# MCU.net
KiCad netlist of a schematic drawn in Altium Designer
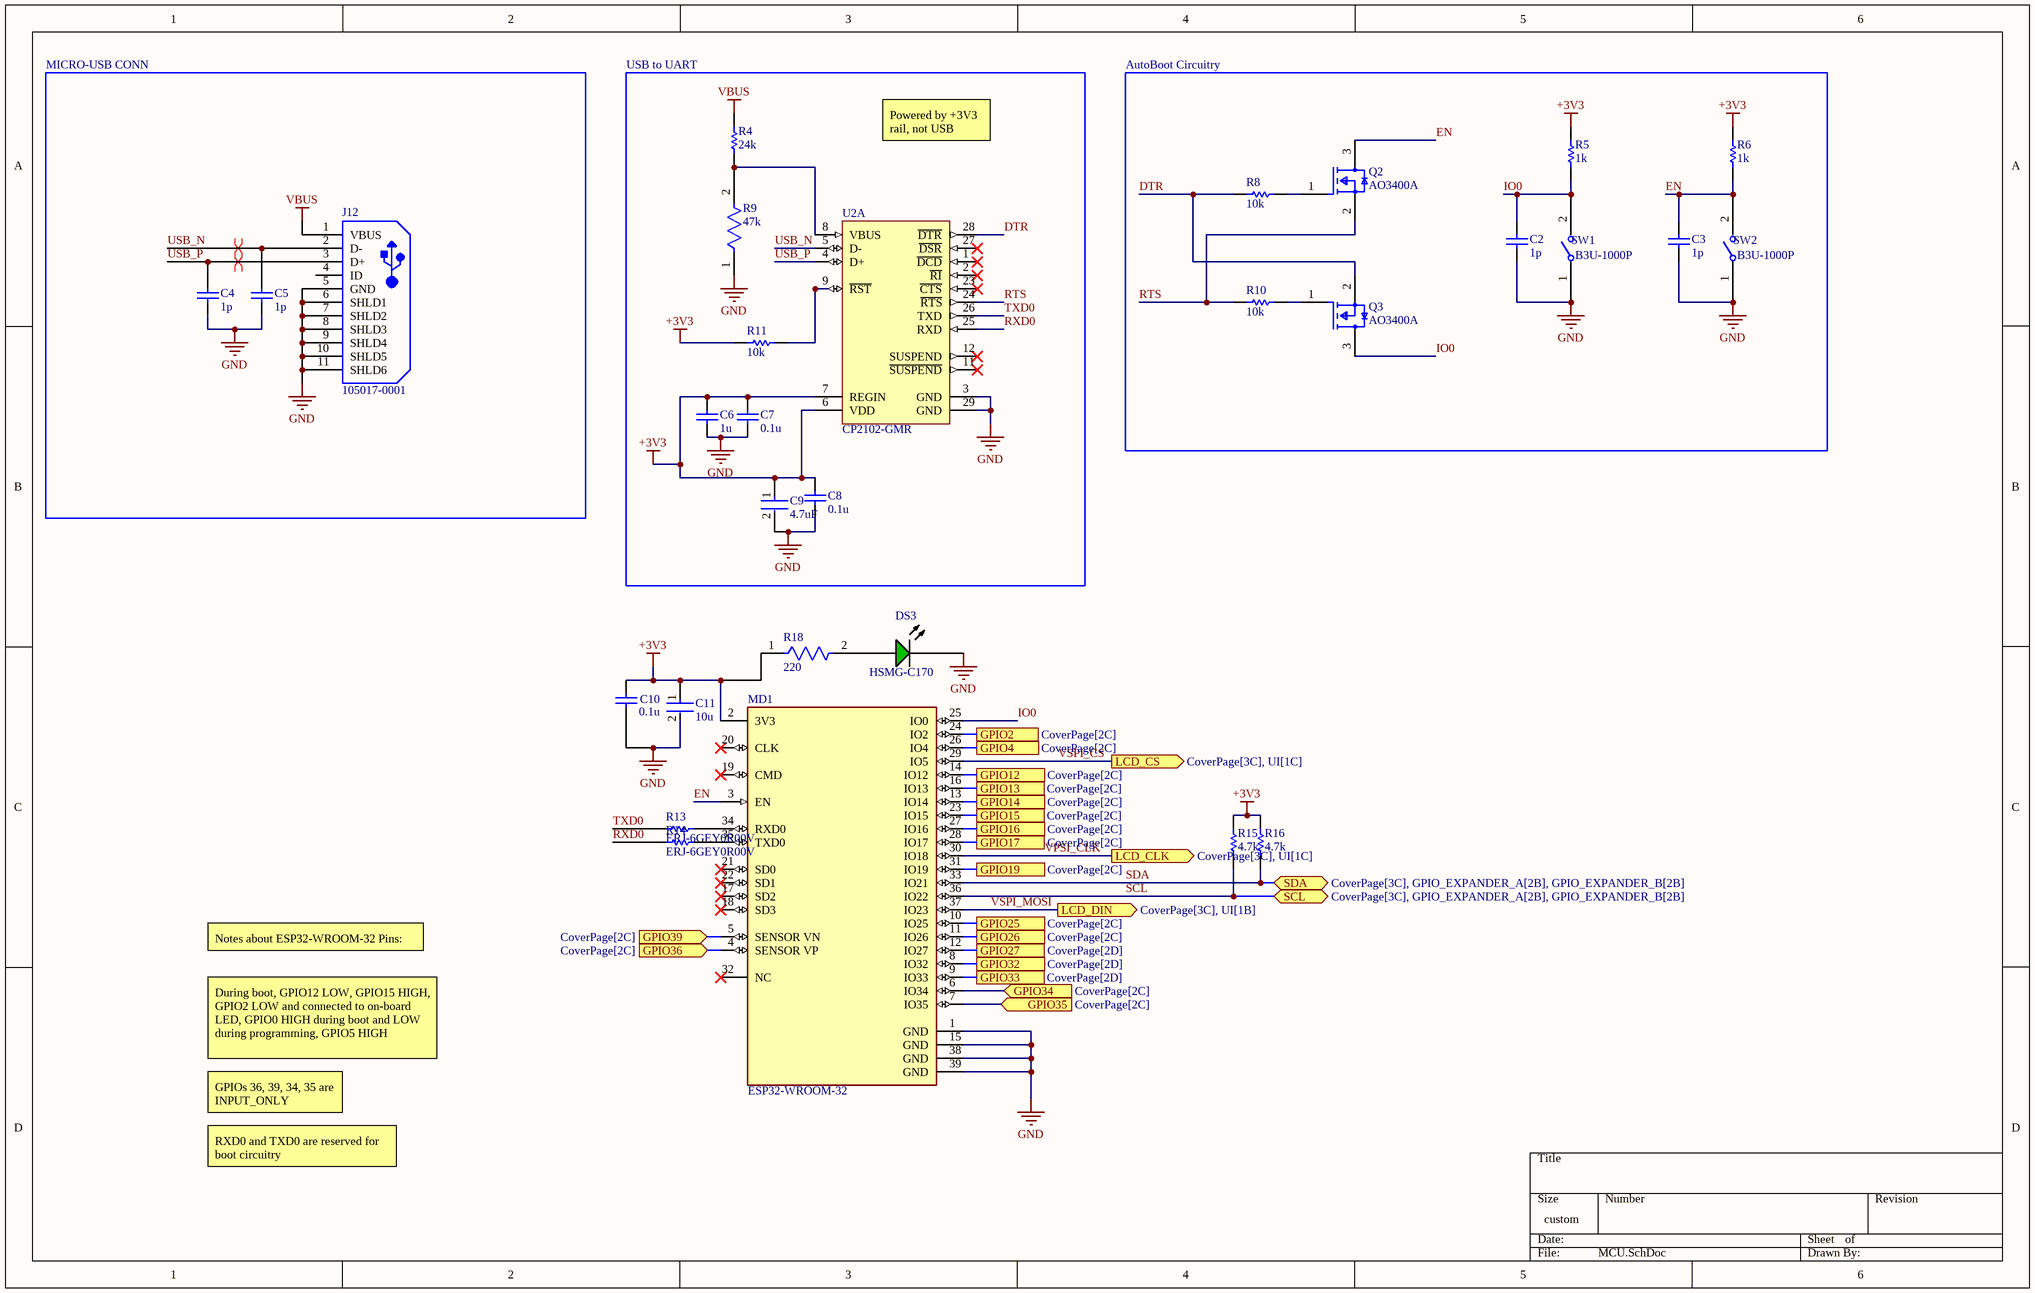
[diagram p0: MCU.SchDoc]

(export (version "E")
  (design (tool "Eeschema 10.0.6"))
  (components
    (comp (ref "C2")
      (value "1p")
      (footprint "CAPC2013X140X50LL20T25")
      (fields
        (field (name "PART NUMBER") "08055A1R0CAT2A")
        (field (name "MANUFACTURER") "AVX Interconnect / Elco")
      )
      (libsource (lib "Altium Content Vault") (part "CAP"))
    )
    (comp (ref "C3")
      (value "1p")
      (footprint "CAPC2013X140X50LL20T25")
      (fields
        (field (name "PART NUMBER") "08055A1R0CAT2A")
        (field (name "MANUFACTURER") "AVX Interconnect / Elco")
      )
      (libsource (lib "Altium Content Vault") (part "CAP"))
    )
    (comp (ref "C4")
      (value "1p")
      (footprint "CAPC2013X140X50LL20T25")
      (fields
        (field (name "PART NUMBER") "08055A1R0CAT2A")
        (field (name "MANUFACTURER") "AVX Interconnect / Elco")
      )
      (libsource (lib "Altium Content Vault") (part "CAP"))
    )
    (comp (ref "C5")
      (value "1p")
      (footprint "CAPC2013X140X50LL20T25")
      (fields
        (field (name "PART NUMBER") "08055A1R0CAT2A")
        (field (name "MANUFACTURER") "AVX Interconnect / Elco")
      )
      (libsource (lib "Altium Content Vault") (part "CAP"))
    )
    (comp (ref "C6")
      (value "1u")
      (footprint "CAPC2013X145X50LL20T25")
      (fields (field (name "MANUFACTURER") "Kemet") (field (name "PART NUMBER") "C0805C105K4PACTU"))
      (libsource (lib "Altium Content Vault") (part "CAP"))
    )
    (comp (ref "C7")
      (value "0.1u")
      (footprint "CAPC2013X94X50LL20T25")
      (fields
        (field (name "MANUFACTURER") "AVX Interconnect / Elco")
        (field (name "PART NUMBER") "08055C104JAZ2A")
      )
      (libsource (lib "Altium Content Vault") (part "CAP"))
    )
    (comp (ref "C8")
      (value "0.1u")
      (footprint "CAPC2013X94X50LL20T25")
      (fields
        (field (name "MANUFACTURER") "AVX Interconnect / Elco")
        (field (name "PART NUMBER") "08055C104JAZ2A")
      )
      (libsource (lib "Altium Content Vault") (part "CAP"))
    )
    (comp (ref "C9")
      (value "4.7uF")
      (footprint "FP-CL21-IPC_A")
      (description "CL21 Series 0805 4.7uF 25V ±10% Tolerance X5R Multilayer Ceramic Chip Capacitor")
      (fields (field (name "TOLERANCE") "10%"))
      (libsource (lib "Altium Content Vault") (part "b4654b650e69147ec39a6b967a45e02"))
    )
    (comp (ref "C10")
      (value "0.1u")
      (footprint "CAPC2013X94X50LL20T25")
      (fields
        (field (name "MANUFACTURER") "AVX Interconnect / Elco")
        (field (name "PART NUMBER") "08055C104JAZ2A")
      )
      (libsource (lib "Altium Content Vault") (part "CAP"))
    )
    (comp (ref "C11")
      (value "10u")
      (footprint "FP-C0805C-DG-MFG")
      (description "CAP CER 10UF 10V X5R 0805")
      (fields (field (name "TOLERANCE") "10%") (field (name "MANUFACTURER PART NUMBER") "C0805C106K8PACTU"))
      (libsource (lib "Altium Content Vault") (part "11868f565c42a9108669ba33697ecf6"))
    )
    (comp (ref "DS3")
      (value "HSMG-C170")
      (footprint "AVAG-HSMX-C170_V")
      (description "Chip LED, Green, 2.2 V, -40 to 85 degC, 2-Pin SMD, Pb-Free, Tape and Reel")
      (fields (field (name "MANUFACTURER") "Avago"))
      (libsource (lib "Altium Content Vault") (part "LED_GREEN_A1K2-2"))
    )
    (comp (ref "J12")
      (value "105017-0001")
      (footprint "USB-MICRO-B_V")
      (fields (field (name "MANUFACTURER") "Molex"))
      (libsource (lib "Altium Content Vault") (part "USB-5-6SHLD"))
    )
    (comp (ref "MD1")
      (value "ESP32-WROOM-32")
      (footprint "FP-ESP32-WROOM-32-MFG")
      (description "RX TXRX MOD WIFI SURFACE MOUNT")
      (libsource (lib "Altium Content Vault") (part "ee866abf0b6c51247b7f5cdebf2f250"))
    )
    (comp (ref "Q2")
      (value "AO3400A")
      (footprint "FP-SOT23-MFG")
      (description "MOSFET N-CH 30V 5.7A SOT23")
      (libsource (lib "Altium Content Vault") (part "0a9ea7c96deaaede766a5b531c28de0"))
    )
    (comp (ref "Q3")
      (value "AO3400A")
      (footprint "FP-SOT23-MFG")
      (description "MOSFET N-CH 30V 5.7A SOT23")
      (libsource (lib "Altium Content Vault") (part "0a9ea7c96deaaede766a5b531c28de0"))
    )
    (comp (ref "R4")
      (value "24k")
      (footprint "RESC2013X60X40LL20T25")
      (fields (field (name "PART NUMBER") "ERA6AEB243V") (field (name "MANUFACTURER") "Panasonic"))
      (libsource (lib "Altium Content Vault") (part "RES"))
    )
    (comp (ref "R5")
      (value "1k")
      (footprint "RESC2013X60X35ML10T20")
      (description "Chip Resistor, 1 KOhm, +/- 1%, 125 mW, -55 to 155 degC, 0805 (2012 Metric), RoHS, Tape and Reel")
      (fields (field (name "TOLERANCE") "1%") (field (name "MANUFACTURER") "Yageo"))
      (libsource (lib "Altium Content Vault") (part "RES-2"))
    )
    (comp (ref "R6")
      (value "1k")
      (footprint "RESC2013X60X35ML10T20")
      (description "Chip Resistor, 1 KOhm, +/- 1%, 125 mW, -55 to 155 degC, 0805 (2012 Metric), RoHS, Tape and Reel")
      (fields (field (name "TOLERANCE") "1%") (field (name "MANUFACTURER") "Yageo"))
      (libsource (lib "Altium Content Vault") (part "RES-2"))
    )
    (comp (ref "R8")
      (value "10k")
      (footprint "RESC2013X60X40LL20T25_A")
      (fields (field (name "TOLERANCE") "0.1%") (field (name "MANUFACTURER") "Panasonic"))
      (libsource (lib "Altium Content Vault") (part "RES-2"))
    )
    (comp (ref "R9")
      (value "47k")
      (footprint "FP-ERA6A-MFG")
      (fields (field (name "TOLERANCE") "0.1%"))
      (libsource (lib "Altium Content Vault") (part "1029c3af85768c4190bb7ad29bc67b5"))
    )
    (comp (ref "R10")
      (value "10k")
      (footprint "RESC2013X60X40LL20T25_A")
      (fields (field (name "TOLERANCE") "0.1%") (field (name "MANUFACTURER") "Panasonic"))
      (libsource (lib "Altium Content Vault") (part "RES-2"))
    )
    (comp (ref "R11")
      (value "10k")
      (footprint "RESC2013X60X40LL20T25_A")
      (fields (field (name "TOLERANCE") "0.1%") (field (name "MANUFACTURER") "Panasonic"))
      (libsource (lib "Altium Content Vault") (part "RES-2"))
    )
    (comp (ref "R13")
      (value "ERJ-6GEY0R00V")
      (footprint "RESC2013X70X40NL20T20")
      (description "Chip Resistor, 0 Ohm, +/- 1%, 0.125 W, -55 to 155 degC, 0805 (2012 Metric), RoHS, Tape and Reel")
      (fields (field (name "TOLERANCE") "5%"))
      (libsource (lib "Altium Content Vault") (part "RES-2"))
    )
    (comp (ref "R14")
      (value "ERJ-6GEY0R00V")
      (footprint "RESC2013X70X40NL20T20")
      (description "Chip Resistor, 0 Ohm, +/- 1%, 0.125 W, -55 to 155 degC, 0805 (2012 Metric), RoHS, Tape and Reel")
      (fields (field (name "TOLERANCE") "5%"))
      (libsource (lib "Altium Content Vault") (part "RES-2"))
    )
    (comp (ref "R15")
      (value "4.7k")
      (footprint "YAGO-RC0805_M")
      (fields
        (field (name "TOLERANCE") "+/- 1%")
        (field (name "PARTNUMBER") "RC0805FR-074K7L")
        (field (name "POWER") "0.125 W")
      )
      (libsource (lib "Altium Content Vault") (part "YAGO-RES-2"))
    )
    (comp (ref "R16")
      (value "4.7k")
      (footprint "YAGO-RC0805_M")
      (fields
        (field (name "TOLERANCE") "+/- 1%")
        (field (name "PARTNUMBER") "RC0805FR-074K7L")
        (field (name "POWER") "0.125 W")
      )
      (libsource (lib "Altium Content Vault") (part "YAGO-RES-2"))
    )
    (comp (ref "R18")
      (value "220")
      (footprint "FP-CRCW0805-e3-MFG")
      (description "RES Thick Film, 330Ω, 1%, 0.125W, 100ppm/°C, 0805")
      (fields (field (name "TOLERANCE") "1%"))
      (libsource (lib "Altium Content Vault") (part "1029c3af85768c4190bb7ad29bc67b5"))
    )
    (comp (ref "SW1")
      (value "B3U-1000P")
      (footprint "FP-B3U-1000P-MFG")
      (description "SWITCH TACTILE SPST-NO 0.05A 12V")
      (libsource (lib "Altium Content Vault") (part "ae622034201233ca1abcedc05908f33"))
    )
    (comp (ref "SW2")
      (value "B3U-1000P")
      (footprint "FP-B3U-1000P-MFG")
      (description "SWITCH TACTILE SPST-NO 0.05A 12V")
      (libsource (lib "Altium Content Vault") (part "ae622034201233ca1abcedc05908f33"))
    )
    (comp (ref "U2")
      (value "CP2102-GMR")
      (footprint "SLAB-QFN-28-3125x3125TP_M")
      (description "Single-Chip USB to URAT Bridge, 3.3 V, -40 to 85 degC, 28-Pin QFN, RoHS, Tape and Reel")
      (fields (field (name "MANUFACTURER") "Silicon Labs"))
      (libsource (lib "Altium Content Vault") (part "SLAB-CP210X-QFN-28-29"))
    )
  )
  (nets
    (net (code "1") (name "+3V3") (class "Default")
      (node (ref "C10") (pin "2") (pinfunction "2_2") (pintype "passive"))
      (node (ref "C11") (pin "1") (pinfunction "1_1") (pintype "passive"))
      (node (ref "C6") (pin "2") (pinfunction "2_2") (pintype "passive"))
      (node (ref "C7") (pin "2") (pinfunction "2_2") (pintype "passive"))
      (node (ref "C8") (pin "2") (pinfunction "2_2") (pintype "passive"))
      (node (ref "C9") (pin "1") (pinfunction "1_1") (pintype "passive"))
      (node (ref "MD1") (pin "2") (pinfunction "3V3_2") (pintype "power_in"))
      (node (ref "R11") (pin "1") (pinfunction "1_1") (pintype "passive"))
      (node (ref "R15") (pin "2") (pinfunction "2_2") (pintype "passive"))
      (node (ref "R16") (pin "2") (pinfunction "2_2") (pintype "passive"))
      (node (ref "R18") (pin "1") (pinfunction "1_1") (pintype "passive"))
      (node (ref "R5") (pin "2") (pinfunction "2_2") (pintype "passive"))
      (node (ref "R6") (pin "2") (pinfunction "2_2") (pintype "passive"))
      (node (ref "U2") (pin "6") (pinfunction "VDD_6") (pintype "power_in"))
      (node (ref "U2") (pin "7") (pinfunction "REGIN_7") (pintype "power_in"))
    )
    (net (code "2") (name "/DTR") (class "Default")
      (node (ref "Q3") (pin "2") (pinfunction "S_2") (pintype "passive"))
      (node (ref "R8") (pin "1") (pinfunction "1_1") (pintype "passive"))
      (node (ref "U2") (pin "28") (pinfunction "~{DTR}_28") (pintype "output"))
    )
    (net (code "3") (name "/EN") (class "Default")
      (node (ref "C3") (pin "2") (pinfunction "2_2") (pintype "passive"))
      (node (ref "MD1") (pin "3") (pinfunction "EN_3") (pintype "input"))
      (node (ref "Q2") (pin "3") (pinfunction "D_3") (pintype "passive"))
      (node (ref "R6") (pin "1") (pinfunction "1_1") (pintype "passive"))
      (node (ref "SW2") (pin "2") (pinfunction "2_2") (pintype "passive"))
    )
    (net (code "4") (name "/GPIO2") (class "Default")
      (node (ref "MD1") (pin "24") (pinfunction "IO2_24") (pintype "bidirectional"))
    )
    (net (code "5") (name "/GPIO4") (class "Default")
      (node (ref "MD1") (pin "26") (pinfunction "IO4_26") (pintype "bidirectional"))
    )
    (net (code "6") (name "/GPIO12") (class "Default")
      (node (ref "MD1") (pin "14") (pinfunction "IO12_14") (pintype "bidirectional"))
    )
    (net (code "7") (name "/GPIO13") (class "Default")
      (node (ref "MD1") (pin "16") (pinfunction "IO13_16") (pintype "bidirectional"))
    )
    (net (code "8") (name "/GPIO14") (class "Default")
      (node (ref "MD1") (pin "13") (pinfunction "IO14_13") (pintype "bidirectional"))
    )
    (net (code "9") (name "/GPIO15") (class "Default")
      (node (ref "MD1") (pin "23") (pinfunction "IO15_23") (pintype "bidirectional"))
    )
    (net (code "10") (name "/GPIO16") (class "Default")
      (node (ref "MD1") (pin "27") (pinfunction "IO16_27") (pintype "bidirectional"))
    )
    (net (code "11") (name "/GPIO17") (class "Default")
      (node (ref "MD1") (pin "28") (pinfunction "IO17_28") (pintype "bidirectional"))
    )
    (net (code "12") (name "/GPIO19") (class "Default")
      (node (ref "MD1") (pin "31") (pinfunction "IO19_31") (pintype "bidirectional"))
    )
    (net (code "13") (name "/GPIO25") (class "Default")
      (node (ref "MD1") (pin "10") (pinfunction "IO25_10") (pintype "bidirectional"))
    )
    (net (code "14") (name "/GPIO26") (class "Default")
      (node (ref "MD1") (pin "11") (pinfunction "IO26_11") (pintype "bidirectional"))
    )
    (net (code "15") (name "/GPIO27") (class "Default")
      (node (ref "MD1") (pin "12") (pinfunction "IO27_12") (pintype "bidirectional"))
    )
    (net (code "16") (name "/GPIO32") (class "Default")
      (node (ref "MD1") (pin "8") (pinfunction "IO32_8") (pintype "bidirectional"))
    )
    (net (code "17") (name "/GPIO33") (class "Default")
      (node (ref "MD1") (pin "9") (pinfunction "IO33_9") (pintype "bidirectional"))
    )
    (net (code "18") (name "/GPIO34") (class "Default")
      (node (ref "MD1") (pin "6") (pinfunction "IO34_6") (pintype "bidirectional"))
    )
    (net (code "19") (name "/GPIO35") (class "Default")
      (node (ref "MD1") (pin "7") (pinfunction "IO35_7") (pintype "bidirectional"))
    )
    (net (code "20") (name "/GPIO36") (class "Default")
      (node (ref "MD1") (pin "4") (pinfunction "SENSOR_VP_4") (pintype "bidirectional"))
    )
    (net (code "21") (name "/GPIO39") (class "Default")
      (node (ref "MD1") (pin "5") (pinfunction "SENSOR_VN_5") (pintype "bidirectional"))
    )
    (net (code "22") (name "/IO0") (class "Default")
      (node (ref "C2") (pin "2") (pinfunction "2_2") (pintype "passive"))
      (node (ref "MD1") (pin "25") (pinfunction "IO0_25") (pintype "bidirectional"))
      (node (ref "Q3") (pin "3") (pinfunction "D_3") (pintype "passive"))
      (node (ref "R5") (pin "1") (pinfunction "1_1") (pintype "passive"))
      (node (ref "SW1") (pin "2") (pinfunction "2_2") (pintype "passive"))
    )
    (net (code "23") (name "/RTS") (class "Default")
      (node (ref "Q2") (pin "2") (pinfunction "S_2") (pintype "passive"))
      (node (ref "R10") (pin "1") (pinfunction "1_1") (pintype "passive"))
      (node (ref "U2") (pin "24") (pinfunction "~{RTS}_24") (pintype "output"))
    )
    (net (code "24") (name "/RXD0") (class "Default")
      (node (ref "R14") (pin "1") (pinfunction "1_1") (pintype "passive"))
      (node (ref "U2") (pin "25") (pinfunction "RXD_25") (pintype "input"))
    )
    (net (code "25") (name "/SCL") (class "Default")
      (node (ref "MD1") (pin "36") (pinfunction "IO22_36") (pintype "bidirectional"))
      (node (ref "R15") (pin "1") (pinfunction "1_1") (pintype "passive"))
    )
    (net (code "26") (name "/SDA") (class "Default")
      (node (ref "MD1") (pin "33") (pinfunction "IO21_33") (pintype "bidirectional"))
      (node (ref "R16") (pin "1") (pinfunction "1_1") (pintype "passive"))
    )
    (net (code "27") (name "/TXD0") (class "Default")
      (node (ref "R13") (pin "1") (pinfunction "1_1") (pintype "passive"))
      (node (ref "U2") (pin "26") (pinfunction "TXD_26") (pintype "output"))
    )
    (net (code "28") (name "/USB_N") (class "Default")
      (node (ref "C5") (pin "2") (pinfunction "2_2") (pintype "passive"))
      (node (ref "J12") (pin "2") (pinfunction "D-_2") (pintype "passive"))
      (node (ref "U2") (pin "5") (pinfunction "D-_5") (pintype "bidirectional"))
    )
    (net (code "29") (name "/USB_P") (class "Default")
      (node (ref "C4") (pin "2") (pinfunction "2_2") (pintype "passive"))
      (node (ref "J12") (pin "3") (pinfunction "D+_3") (pintype "passive"))
      (node (ref "U2") (pin "4") (pinfunction "D+_4") (pintype "bidirectional"))
    )
    (net (code "30") (name "/VPSI_CLK") (class "Default")
      (node (ref "MD1") (pin "30") (pinfunction "IO18_30") (pintype "bidirectional"))
    )
    (net (code "31") (name "/VSPI_CS") (class "Default")
      (node (ref "MD1") (pin "29") (pinfunction "IO5_29") (pintype "bidirectional"))
    )
    (net (code "32") (name "/VSPI_MOSI") (class "Default")
      (node (ref "MD1") (pin "37") (pinfunction "IO23_37") (pintype "bidirectional"))
    )
    (net (code "33") (name "GND") (class "Default")
      (node (ref "C10") (pin "1") (pinfunction "1_1") (pintype "passive"))
      (node (ref "C11") (pin "2") (pinfunction "2_2") (pintype "passive"))
      (node (ref "C2") (pin "1") (pinfunction "1_1") (pintype "passive"))
      (node (ref "C3") (pin "1") (pinfunction "1_1") (pintype "passive"))
      (node (ref "C4") (pin "1") (pinfunction "1_1") (pintype "passive"))
      (node (ref "C5") (pin "1") (pinfunction "1_1") (pintype "passive"))
      (node (ref "C6") (pin "1") (pinfunction "1_1") (pintype "passive"))
      (node (ref "C7") (pin "1") (pinfunction "1_1") (pintype "passive"))
      (node (ref "C8") (pin "1") (pinfunction "1_1") (pintype "passive"))
      (node (ref "C9") (pin "2") (pinfunction "2_2") (pintype "passive"))
      (node (ref "DS3") (pin "2") (pinfunction "K_2") (pintype "passive"))
      (node (ref "J12") (pin "10") (pinfunction "SHLD5_10") (pintype "passive"))
      (node (ref "J12") (pin "11") (pinfunction "SHLD6_11") (pintype "passive"))
      (node (ref "J12") (pin "5") (pinfunction "GND_5") (pintype "passive"))
      (node (ref "J12") (pin "6") (pinfunction "SHLD1_6") (pintype "passive"))
      (node (ref "J12") (pin "7") (pinfunction "SHLD2_7") (pintype "passive"))
      (node (ref "J12") (pin "8") (pinfunction "SHLD3_8") (pintype "passive"))
      (node (ref "J12") (pin "9") (pinfunction "SHLD4_9") (pintype "passive"))
      (node (ref "MD1") (pin "1") (pinfunction "GND_1") (pintype "power_in"))
      (node (ref "MD1") (pin "15") (pinfunction "GND_15") (pintype "power_in"))
      (node (ref "MD1") (pin "38") (pinfunction "GND_38") (pintype "power_in"))
      (node (ref "MD1") (pin "39") (pinfunction "GND_39") (pintype "power_in"))
      (node (ref "R9") (pin "1") (pinfunction "1_1") (pintype "passive"))
      (node (ref "SW1") (pin "1") (pinfunction "1_1") (pintype "passive"))
      (node (ref "SW2") (pin "1") (pinfunction "1_1") (pintype "passive"))
      (node (ref "U2") (pin "29") (pinfunction "GND_29") (pintype "power_in"))
      (node (ref "U2") (pin "3") (pinfunction "GND_3") (pintype "power_in"))
    )
    (net (code "34") (name "Net-(DS3-A)") (class "Default")
      (node (ref "DS3") (pin "1") (pinfunction "A_1") (pintype "passive"))
      (node (ref "R18") (pin "2") (pinfunction "2_2") (pintype "passive"))
    )
    (net (code "35") (name "Net-(MD1-RXD0)") (class "Default")
      (node (ref "MD1") (pin "34") (pinfunction "RXD0_34") (pintype "bidirectional"))
      (node (ref "R13") (pin "2") (pinfunction "2_2") (pintype "passive"))
    )
    (net (code "36") (name "Net-(MD1-TXD0)") (class "Default")
      (node (ref "MD1") (pin "35") (pinfunction "TXD0_35") (pintype "bidirectional"))
      (node (ref "R14") (pin "2") (pinfunction "2_2") (pintype "passive"))
    )
    (net (code "37") (name "Net-(Q2-G)") (class "Default")
      (node (ref "Q2") (pin "1") (pinfunction "G_1") (pintype "passive"))
      (node (ref "R8") (pin "2") (pinfunction "2_2") (pintype "passive"))
    )
    (net (code "38") (name "Net-(Q3-G)") (class "Default")
      (node (ref "Q3") (pin "1") (pinfunction "G_1") (pintype "passive"))
      (node (ref "R10") (pin "2") (pinfunction "2_2") (pintype "passive"))
    )
    (net (code "39") (name "Net-(U2A-VBUS)") (class "Default")
      (node (ref "R4") (pin "1") (pinfunction "1_1") (pintype "passive"))
      (node (ref "R9") (pin "2") (pinfunction "2_2") (pintype "passive"))
      (node (ref "U2") (pin "8") (pinfunction "VBUS_8") (pintype "input"))
    )
    (net (code "40") (name "Net-(U2A-~{RST})") (class "Default")
      (node (ref "R11") (pin "2") (pinfunction "2_2") (pintype "passive"))
      (node (ref "U2") (pin "9") (pinfunction "~{RST}_9") (pintype "bidirectional"))
    )
    (net (code "41") (name "VBUS") (class "Default")
      (node (ref "J12") (pin "1") (pinfunction "VBUS_1") (pintype "passive"))
      (node (ref "R4") (pin "2") (pinfunction "2_2") (pintype "passive"))
    )
    (net (code "42") (name "unconnected-(J12-ID-Pad4)") (class "Default")
      (node (ref "J12") (pin "4") (pinfunction "ID_4") (pintype "passive"))
    )
    (net (code "43") (name "unconnected-(MD1-CLK-Pad20)") (class "Default")
      (node (ref "MD1") (pin "20") (pinfunction "CLK_20") (pintype "bidirectional+no_connect"))
    )
    (net (code "44") (name "unconnected-(MD1-CMD-Pad19)") (class "Default")
      (node (ref "MD1") (pin "19") (pinfunction "CMD_19") (pintype "bidirectional+no_connect"))
    )
    (net (code "45") (name "unconnected-(MD1-NC-Pad32)") (class "Default")
      (node (ref "MD1") (pin "32") (pinfunction "NC_32") (pintype "passive+no_connect"))
    )
    (net (code "46") (name "unconnected-(MD1-SD0-Pad21)") (class "Default")
      (node (ref "MD1") (pin "21") (pinfunction "SD0_21") (pintype "bidirectional+no_connect"))
    )
    (net (code "47") (name "unconnected-(MD1-SD1-Pad22)") (class "Default")
      (node (ref "MD1") (pin "22") (pinfunction "SD1_22") (pintype "bidirectional+no_connect"))
    )
    (net (code "48") (name "unconnected-(MD1-SD2-Pad17)") (class "Default")
      (node (ref "MD1") (pin "17") (pinfunction "SD2_17") (pintype "bidirectional+no_connect"))
    )
    (net (code "49") (name "unconnected-(MD1-SD3-Pad18)") (class "Default")
      (node (ref "MD1") (pin "18") (pinfunction "SD3_18") (pintype "bidirectional+no_connect"))
    )
    (net (code "50") (name "unconnected-(U2A-SUSPEND-Pad12)") (class "Default")
      (node (ref "U2") (pin "12") (pinfunction "SUSPEND_12") (pintype "output+no_connect"))
    )
    (net (code "51") (name "unconnected-(U2A-~{CTS}-Pad23)") (class "Default")
      (node (ref "U2") (pin "23") (pinfunction "~{CTS}_23") (pintype "input+no_connect"))
    )
    (net (code "52") (name "unconnected-(U2A-~{DCD}-Pad1)") (class "Default")
      (node (ref "U2") (pin "1") (pinfunction "~{DCD}_1") (pintype "input+no_connect"))
    )
    (net (code "53") (name "unconnected-(U2A-~{DSR}-Pad27)") (class "Default")
      (node (ref "U2") (pin "27") (pinfunction "~{DSR}_27") (pintype "input+no_connect"))
    )
    (net (code "54") (name "unconnected-(U2A-~{RI}-Pad2)") (class "Default")
      (node (ref "U2") (pin "2") (pinfunction "~{RI}_2") (pintype "input+no_connect"))
    )
    (net (code "55") (name "unconnected-(U2A-~{SUSPEND}-Pad11)") (class "Default")
      (node (ref "U2") (pin "11") (pinfunction "~{SUSPEND}_11") (pintype "output+no_connect"))
    )
  )
)
